# ats.net
KiCad netlist of a schematic drawn in EAGLE
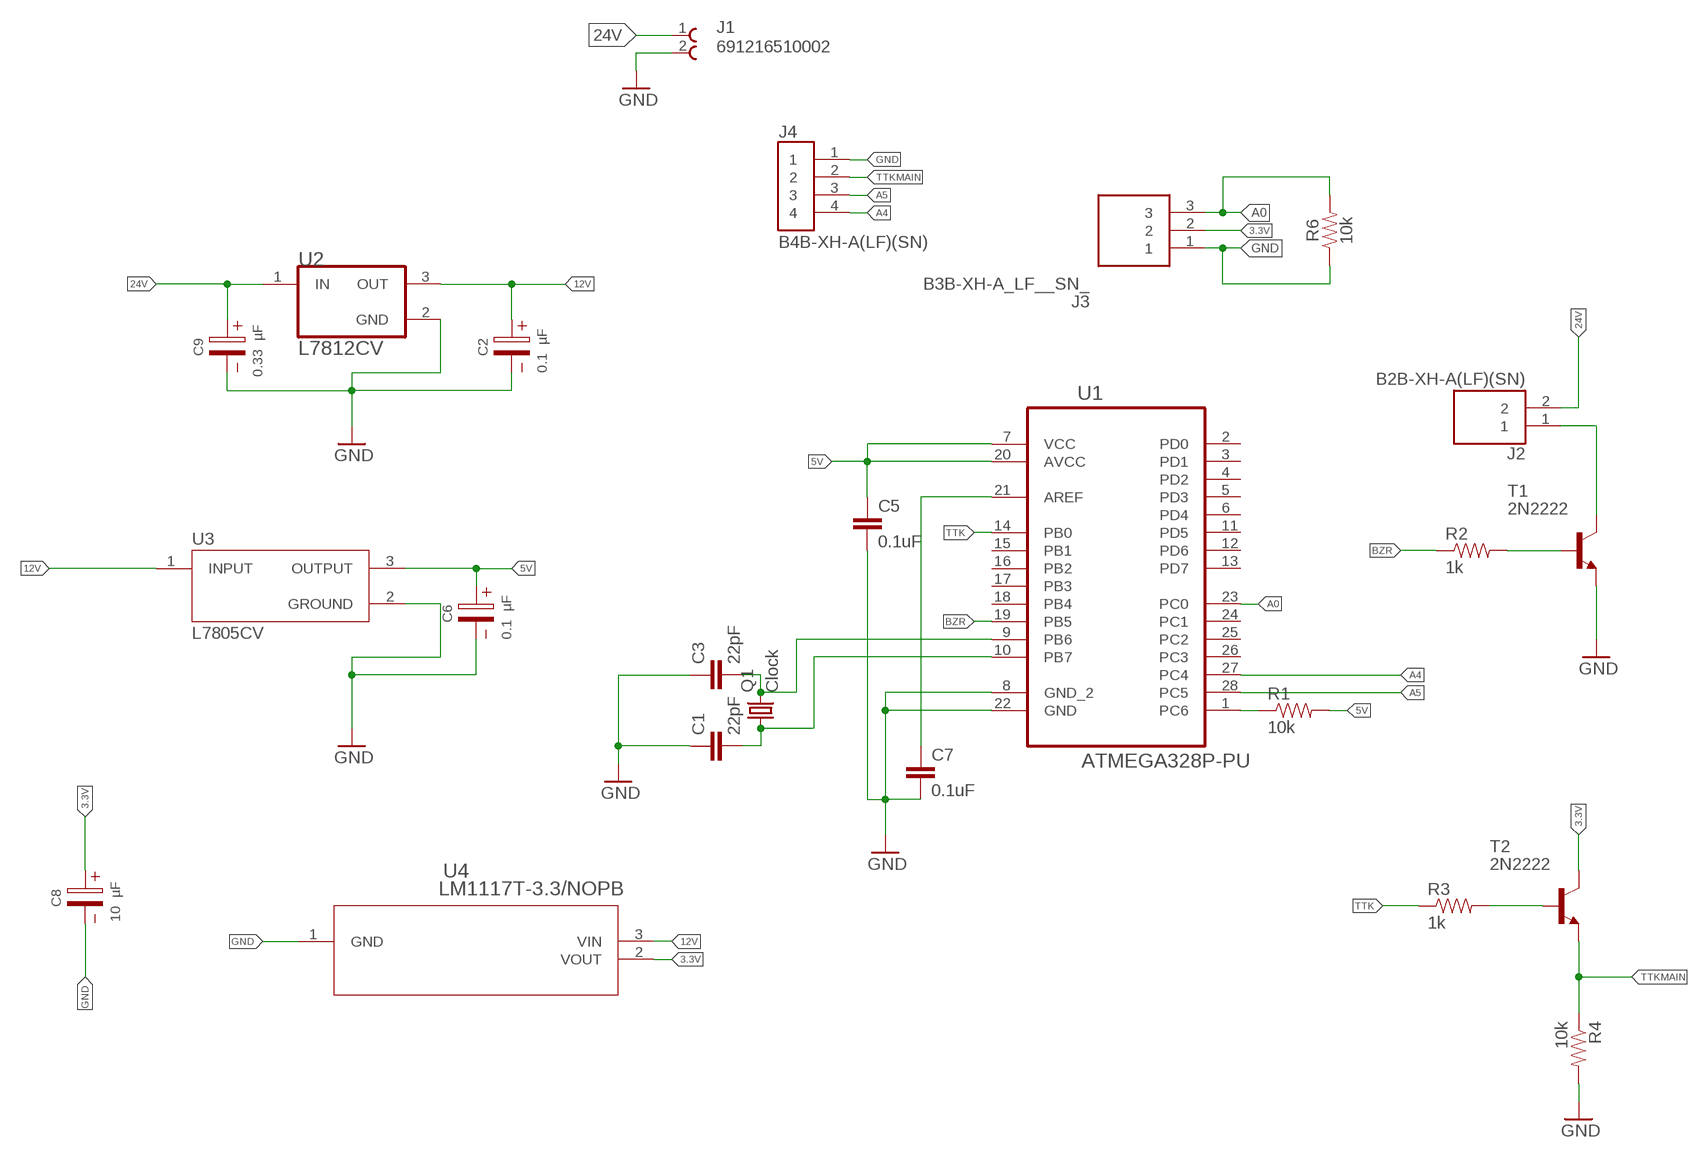
[diagram p0: schematic, sheet 1]

(export (version "E")
  (design (tool "Eeschema 10.0.6"))
  (components
    (comp (ref "C1")
      (value "22pF")
      (footprint "eagle-import:CAP-PTH-2.54")
      (libsource (lib "eagle-import") (part "22PF-PTH-2.54MM-200V-5%"))
    )
    (comp (ref "C2")
      (value "0.1 µF")
      (footprint "eagle-import:WCAP-ATG5_5X11(DXL)")
      (libsource (lib "eagle-import") (part "WCAP-ATG5_5X11_860020772001"))
    )
    (comp (ref "C3")
      (value "22pF")
      (footprint "eagle-import:CAP-PTH-2.54")
      (libsource (lib "eagle-import") (part "22PF-PTH-2.54MM-200V-5%"))
    )
    (comp (ref "C5")
      (value "0.1uF")
      (footprint "eagle-import:CAP-PTH-SMALL-KIT")
      (libsource (lib "eagle-import") (part "0.1UF-KIT-EZ-50V-20%"))
    )
    (comp (ref "C6")
      (value "0.1 µF")
      (footprint "eagle-import:WCAP-ATG5_5X11(DXL)")
      (libsource (lib "eagle-import") (part "WCAP-ATG5_5X11_860020772001"))
    )
    (comp (ref "C7")
      (value "0.1uF")
      (footprint "eagle-import:CAP-PTH-SMALL-KIT")
      (libsource (lib "eagle-import") (part "0.1UF-KIT-EZ-50V-20%"))
    )
    (comp (ref "C8")
      (value "10 µF")
      (footprint "eagle-import:WCAP-ATG5_5X11(DXL)")
      (libsource (lib "eagle-import") (part "WCAP-ATG5_5X11_860020372001"))
    )
    (comp (ref "C9")
      (value "0.33 µF")
      (footprint "eagle-import:WCAP-ATG5_5X11(DXL)")
      (libsource (lib "eagle-import") (part "WCAP-ATG5_5X11_860020772003"))
    )
    (comp (ref "J1")
      (value "691216510002")
      (footprint "eagle-import:691216510002")
      (fields (field (name "MF") "Wurth Electronics"))
      (libsource (lib "eagle-import") (part "691216510002"))
    )
    (comp (ref "J2")
      (value "B2B-XH-A(LF)(SN)")
      (footprint "eagle-import:JST_B2B-XH-A(LF)(SN)")
      (fields (field (name "DIGI-KEY_PART_NUMBER") "455-2247-ND") (field (name "MF") "JST Sales"))
      (libsource (lib "eagle-import") (part "B2B-XH-A(LF)(SN)"))
    )
    (comp (ref "J3")
      (value "B3B-XH-A_LF__SN_")
      (footprint "eagle-import:SHDR3W64P0X250_1X3_990X575X700")
      (fields (field (name "ARROW_PART_NUMBER") "B3B-XH-A(LF)(SN)"))
      (libsource (lib "eagle-import") (part "B3B-XH-A_LF__SN_"))
    )
    (comp (ref "J4")
      (value "B4B-XH-A(LF)(SN)")
      (footprint "eagle-import:JST_B4B-XH-A(LF)(SN)")
      (fields (field (name "DIGI-KEY_PART_NUMBER") "455-2249-ND") (field (name "MF") "JST Sales"))
      (libsource (lib "eagle-import") (part "B4B-XH-A(LF)(SN)"))
    )
    (comp (ref "Q1")
      (value "Clock")
      (footprint "eagle-import:HC49_S")
      (libsource (lib "eagle-import") (part "CRYSTALHC49S"))
    )
    (comp (ref "R1")
      (value "10k")
      (footprint "eagle-import:AXIAL-0.3")
      (libsource (lib "eagle-import") (part "10KOHM-HORIZ-1/4W-5%"))
    )
    (comp (ref "R2")
      (value "1k")
      (footprint "eagle-import:AXIAL-0.3")
      (libsource (lib "eagle-import") (part "1KOHM-HORIZ-1/4W-5%"))
    )
    (comp (ref "R3")
      (value "1k")
      (footprint "eagle-import:AXIAL-0.3")
      (libsource (lib "eagle-import") (part "1KOHM-HORIZ-1/4W-5%"))
    )
    (comp (ref "R4")
      (value "10k")
      (footprint "eagle-import:AXIAL-0.3")
      (libsource (lib "eagle-import") (part "10KOHM-HORIZ-1/4W-5%"))
    )
    (comp (ref "R6")
      (value "10k")
      (footprint "eagle-import:AXIAL-0.3")
      (libsource (lib "eagle-import") (part "10KOHM-HORIZ-1/4W-5%"))
    )
    (comp (ref "T1")
      (value "2N2222")
      (footprint "eagle-import:TO92-EBC-OVAL")
      (libsource (lib "eagle-import") (part "2N2222"))
    )
    (comp (ref "T2")
      (value "2N2222")
      (footprint "eagle-import:TO92-EBC-OVAL")
      (libsource (lib "eagle-import") (part "2N2222"))
    )
    (comp (ref "U1")
      (value "ATMEGA328P-PU")
      (footprint "eagle-import:DIP254P762X457-28")
      (libsource (lib "eagle-import") (part "ATMEGA328P-PU"))
    )
    (comp (ref "U2")
      (value "L7812CV")
      (footprint "eagle-import:TO-220-3")
      (fields (field (name "DIGI-KEY_PART_NUMBER") "497-12406-ND") (field (name "MF") "STMicroelectronics"))
      (libsource (lib "eagle-import") (part "L7812CV"))
    )
    (comp (ref "U3")
      (value "L7805CV")
      (footprint "eagle-import:TO255P1040X460X1968-3")
      (fields (field (name "DIGI-KEY_PART_NUMBER") "497-12404-ND") (field (name "MF") "STMicroelectronics"))
      (libsource (lib "eagle-import") (part "L7805CV"))
    )
    (comp (ref "U4")
      (value "LM1117T-3.3/NOPB")
      (footprint "eagle-import:T03B_TEX")
      (fields (field (name "COPYRIGHT") "Copyright (C) 2018 Accelerated Designs. All rights reserved"))
      (libsource (lib "eagle-import") (part "LM1117T-3.3/NOPB"))
    )
  )
  (nets
    (net (code "1") (name "3.3V") (class "Default")
      (node (ref "C8") (pin "1") (pinfunction "+_1") (pintype "passive"))
      (node (ref "J3") (pin "2") (pinfunction "2_2") (pintype "bidirectional"))
      (node (ref "T2") (pin "C") (pinfunction "C_C") (pintype "passive"))
      (node (ref "U4") (pin "2") (pinfunction "VOUT_2") (pintype "output"))
    )
    (net (code "2") (name "5V") (class "Default")
      (node (ref "C5") (pin "1") (pinfunction "1_1") (pintype "passive"))
      (node (ref "C6") (pin "1") (pinfunction "+_1") (pintype "passive"))
      (node (ref "R1") (pin "P$2") (pinfunction "2_P$2") (pintype "passive"))
      (node (ref "U1") (pin "20") (pinfunction "AVCC_20") (pintype "power_in"))
      (node (ref "U1") (pin "7") (pinfunction "VCC_7") (pintype "power_in"))
      (node (ref "U3") (pin "3") (pinfunction "OUTPUT_3") (pintype "output"))
    )
    (net (code "3") (name "12V") (class "Default")
      (node (ref "C2") (pin "1") (pinfunction "+_1") (pintype "passive"))
      (node (ref "U2") (pin "3") (pinfunction "OUT_3") (pintype "output"))
      (node (ref "U3") (pin "1") (pinfunction "INPUT_1") (pintype "input"))
      (node (ref "U4") (pin "3") (pinfunction "VIN_3") (pintype "input"))
    )
    (net (code "4") (name "24V") (class "Default")
      (node (ref "C9") (pin "1") (pinfunction "+_1") (pintype "passive"))
      (node (ref "J1") (pin "1") (pinfunction "1_1") (pintype "passive"))
      (node (ref "J2") (pin "2") (pinfunction "2_2") (pintype "passive"))
      (node (ref "U2") (pin "1") (pinfunction "IN_1") (pintype "input"))
    )
    (net (code "5") (name "A0") (class "Default")
      (node (ref "J3") (pin "3") (pinfunction "3_3") (pintype "bidirectional"))
      (node (ref "R6") (pin "P$2") (pinfunction "2_P$2") (pintype "passive"))
      (node (ref "U1") (pin "23") (pinfunction "PC0_23") (pintype "bidirectional"))
    )
    (net (code "6") (name "A4") (class "Default")
      (node (ref "J4") (pin "4") (pinfunction "4_4") (pintype "passive"))
      (node (ref "U1") (pin "27") (pinfunction "PC4_27") (pintype "bidirectional"))
    )
    (net (code "7") (name "A5") (class "Default")
      (node (ref "J4") (pin "3") (pinfunction "3_3") (pintype "passive"))
      (node (ref "U1") (pin "28") (pinfunction "PC5_28") (pintype "bidirectional"))
    )
    (net (code "8") (name "BZR") (class "Default")
      (node (ref "R2") (pin "P$1") (pinfunction "1_P$1") (pintype "passive"))
      (node (ref "U1") (pin "19") (pinfunction "PB5_19") (pintype "bidirectional"))
    )
    (net (code "9") (name "GND") (class "Default")
      (node (ref "C1") (pin "1") (pinfunction "1_1") (pintype "passive"))
      (node (ref "C2") (pin "2") (pinfunction "-_2") (pintype "passive"))
      (node (ref "C3") (pin "1") (pinfunction "1_1") (pintype "passive"))
      (node (ref "C5") (pin "2") (pinfunction "2_2") (pintype "passive"))
      (node (ref "C6") (pin "2") (pinfunction "-_2") (pintype "passive"))
      (node (ref "C7") (pin "2") (pinfunction "2_2") (pintype "passive"))
      (node (ref "C8") (pin "2") (pinfunction "-_2") (pintype "passive"))
      (node (ref "C9") (pin "2") (pinfunction "-_2") (pintype "passive"))
      (node (ref "J1") (pin "2") (pinfunction "2_2") (pintype "passive"))
      (node (ref "J3") (pin "1") (pinfunction "1_1") (pintype "bidirectional"))
      (node (ref "J4") (pin "1") (pinfunction "1_1") (pintype "passive"))
      (node (ref "R4") (pin "P$2") (pinfunction "2_P$2") (pintype "passive"))
      (node (ref "R6") (pin "P$1") (pinfunction "1_P$1") (pintype "passive"))
      (node (ref "T1") (pin "E") (pinfunction "E_E") (pintype "passive"))
      (node (ref "U1") (pin "22") (pinfunction "GND_22") (pintype "passive"))
      (node (ref "U1") (pin "8") (pinfunction "GND_2_8") (pintype "passive"))
      (node (ref "U2") (pin "2") (pinfunction "GND_2") (pintype "power_in"))
      (node (ref "U3") (pin "2") (pinfunction "GROUND_2") (pintype "power_in"))
      (node (ref "U4") (pin "1") (pinfunction "GND_1") (pintype "power_in"))
    )
    (net (code "10") (name "Net-(J2-Pad1)") (class "Default")
      (node (ref "J2") (pin "1") (pinfunction "1_1") (pintype "passive"))
      (node (ref "T1") (pin "C") (pinfunction "C_C") (pintype "passive"))
    )
    (net (code "11") (name "Net-(R1-1)") (class "Default")
      (node (ref "R1") (pin "P$1") (pinfunction "1_P$1") (pintype "passive"))
      (node (ref "U1") (pin "1") (pinfunction "PC6_1") (pintype "bidirectional"))
    )
    (net (code "12") (name "Net-(R2-2)") (class "Default")
      (node (ref "R2") (pin "P$2") (pinfunction "2_P$2") (pintype "passive"))
      (node (ref "T1") (pin "B") (pinfunction "B_B") (pintype "passive"))
    )
    (net (code "13") (name "Net-(R3-2)") (class "Default")
      (node (ref "R3") (pin "P$2") (pinfunction "2_P$2") (pintype "passive"))
      (node (ref "T2") (pin "B") (pinfunction "B_B") (pintype "passive"))
    )
    (net (code "14") (name "Net-(U1-AREF)") (class "Default")
      (node (ref "C7") (pin "1") (pinfunction "1_1") (pintype "passive"))
      (node (ref "U1") (pin "21") (pinfunction "AREF_21") (pintype "input"))
    )
    (net (code "15") (name "Net-(U1-PB6)") (class "Default")
      (node (ref "C3") (pin "2") (pinfunction "2_2") (pintype "passive"))
      (node (ref "Q1") (pin "2") (pinfunction "2_2") (pintype "passive"))
      (node (ref "U1") (pin "9") (pinfunction "PB6_9") (pintype "bidirectional"))
    )
    (net (code "16") (name "Net-(U1-PB7)") (class "Default")
      (node (ref "C1") (pin "2") (pinfunction "2_2") (pintype "passive"))
      (node (ref "Q1") (pin "1") (pinfunction "1_1") (pintype "passive"))
      (node (ref "U1") (pin "10") (pinfunction "PB7_10") (pintype "bidirectional"))
    )
    (net (code "17") (name "TTK") (class "Default")
      (node (ref "R3") (pin "P$1") (pinfunction "1_P$1") (pintype "passive"))
      (node (ref "U1") (pin "14") (pinfunction "PB0_14") (pintype "bidirectional"))
    )
    (net (code "18") (name "TTKMAIN") (class "Default")
      (node (ref "J4") (pin "2") (pinfunction "2_2") (pintype "passive"))
      (node (ref "R4") (pin "P$1") (pinfunction "1_P$1") (pintype "passive"))
      (node (ref "T2") (pin "E") (pinfunction "E_E") (pintype "passive"))
    )
    (net (code "19") (name "unconnected-(U1-PB1-Pad15)") (class "Default")
      (node (ref "U1") (pin "15") (pinfunction "PB1_15") (pintype "bidirectional"))
    )
    (net (code "20") (name "unconnected-(U1-PB2-Pad16)") (class "Default")
      (node (ref "U1") (pin "16") (pinfunction "PB2_16") (pintype "bidirectional"))
    )
    (net (code "21") (name "unconnected-(U1-PB3-Pad17)") (class "Default")
      (node (ref "U1") (pin "17") (pinfunction "PB3_17") (pintype "bidirectional"))
    )
    (net (code "22") (name "unconnected-(U1-PB4-Pad18)") (class "Default")
      (node (ref "U1") (pin "18") (pinfunction "PB4_18") (pintype "bidirectional"))
    )
    (net (code "23") (name "unconnected-(U1-PC1-Pad24)") (class "Default")
      (node (ref "U1") (pin "24") (pinfunction "PC1_24") (pintype "bidirectional"))
    )
    (net (code "24") (name "unconnected-(U1-PC2-Pad25)") (class "Default")
      (node (ref "U1") (pin "25") (pinfunction "PC2_25") (pintype "bidirectional"))
    )
    (net (code "25") (name "unconnected-(U1-PC3-Pad26)") (class "Default")
      (node (ref "U1") (pin "26") (pinfunction "PC3_26") (pintype "bidirectional"))
    )
    (net (code "26") (name "unconnected-(U1-PD0-Pad2)") (class "Default")
      (node (ref "U1") (pin "2") (pinfunction "PD0_2") (pintype "bidirectional"))
    )
    (net (code "27") (name "unconnected-(U1-PD1-Pad3)") (class "Default")
      (node (ref "U1") (pin "3") (pinfunction "PD1_3") (pintype "bidirectional"))
    )
    (net (code "28") (name "unconnected-(U1-PD2-Pad4)") (class "Default")
      (node (ref "U1") (pin "4") (pinfunction "PD2_4") (pintype "bidirectional"))
    )
    (net (code "29") (name "unconnected-(U1-PD3-Pad5)") (class "Default")
      (node (ref "U1") (pin "5") (pinfunction "PD3_5") (pintype "bidirectional"))
    )
    (net (code "30") (name "unconnected-(U1-PD4-Pad6)") (class "Default")
      (node (ref "U1") (pin "6") (pinfunction "PD4_6") (pintype "bidirectional"))
    )
    (net (code "31") (name "unconnected-(U1-PD5-Pad11)") (class "Default")
      (node (ref "U1") (pin "11") (pinfunction "PD5_11") (pintype "bidirectional"))
    )
    (net (code "32") (name "unconnected-(U1-PD6-Pad12)") (class "Default")
      (node (ref "U1") (pin "12") (pinfunction "PD6_12") (pintype "bidirectional"))
    )
    (net (code "33") (name "unconnected-(U1-PD7-Pad13)") (class "Default")
      (node (ref "U1") (pin "13") (pinfunction "PD7_13") (pintype "bidirectional"))
    )
  )
)
